# 2_cpu_control.net
KiCad netlist of a schematic drawn in EAGLE
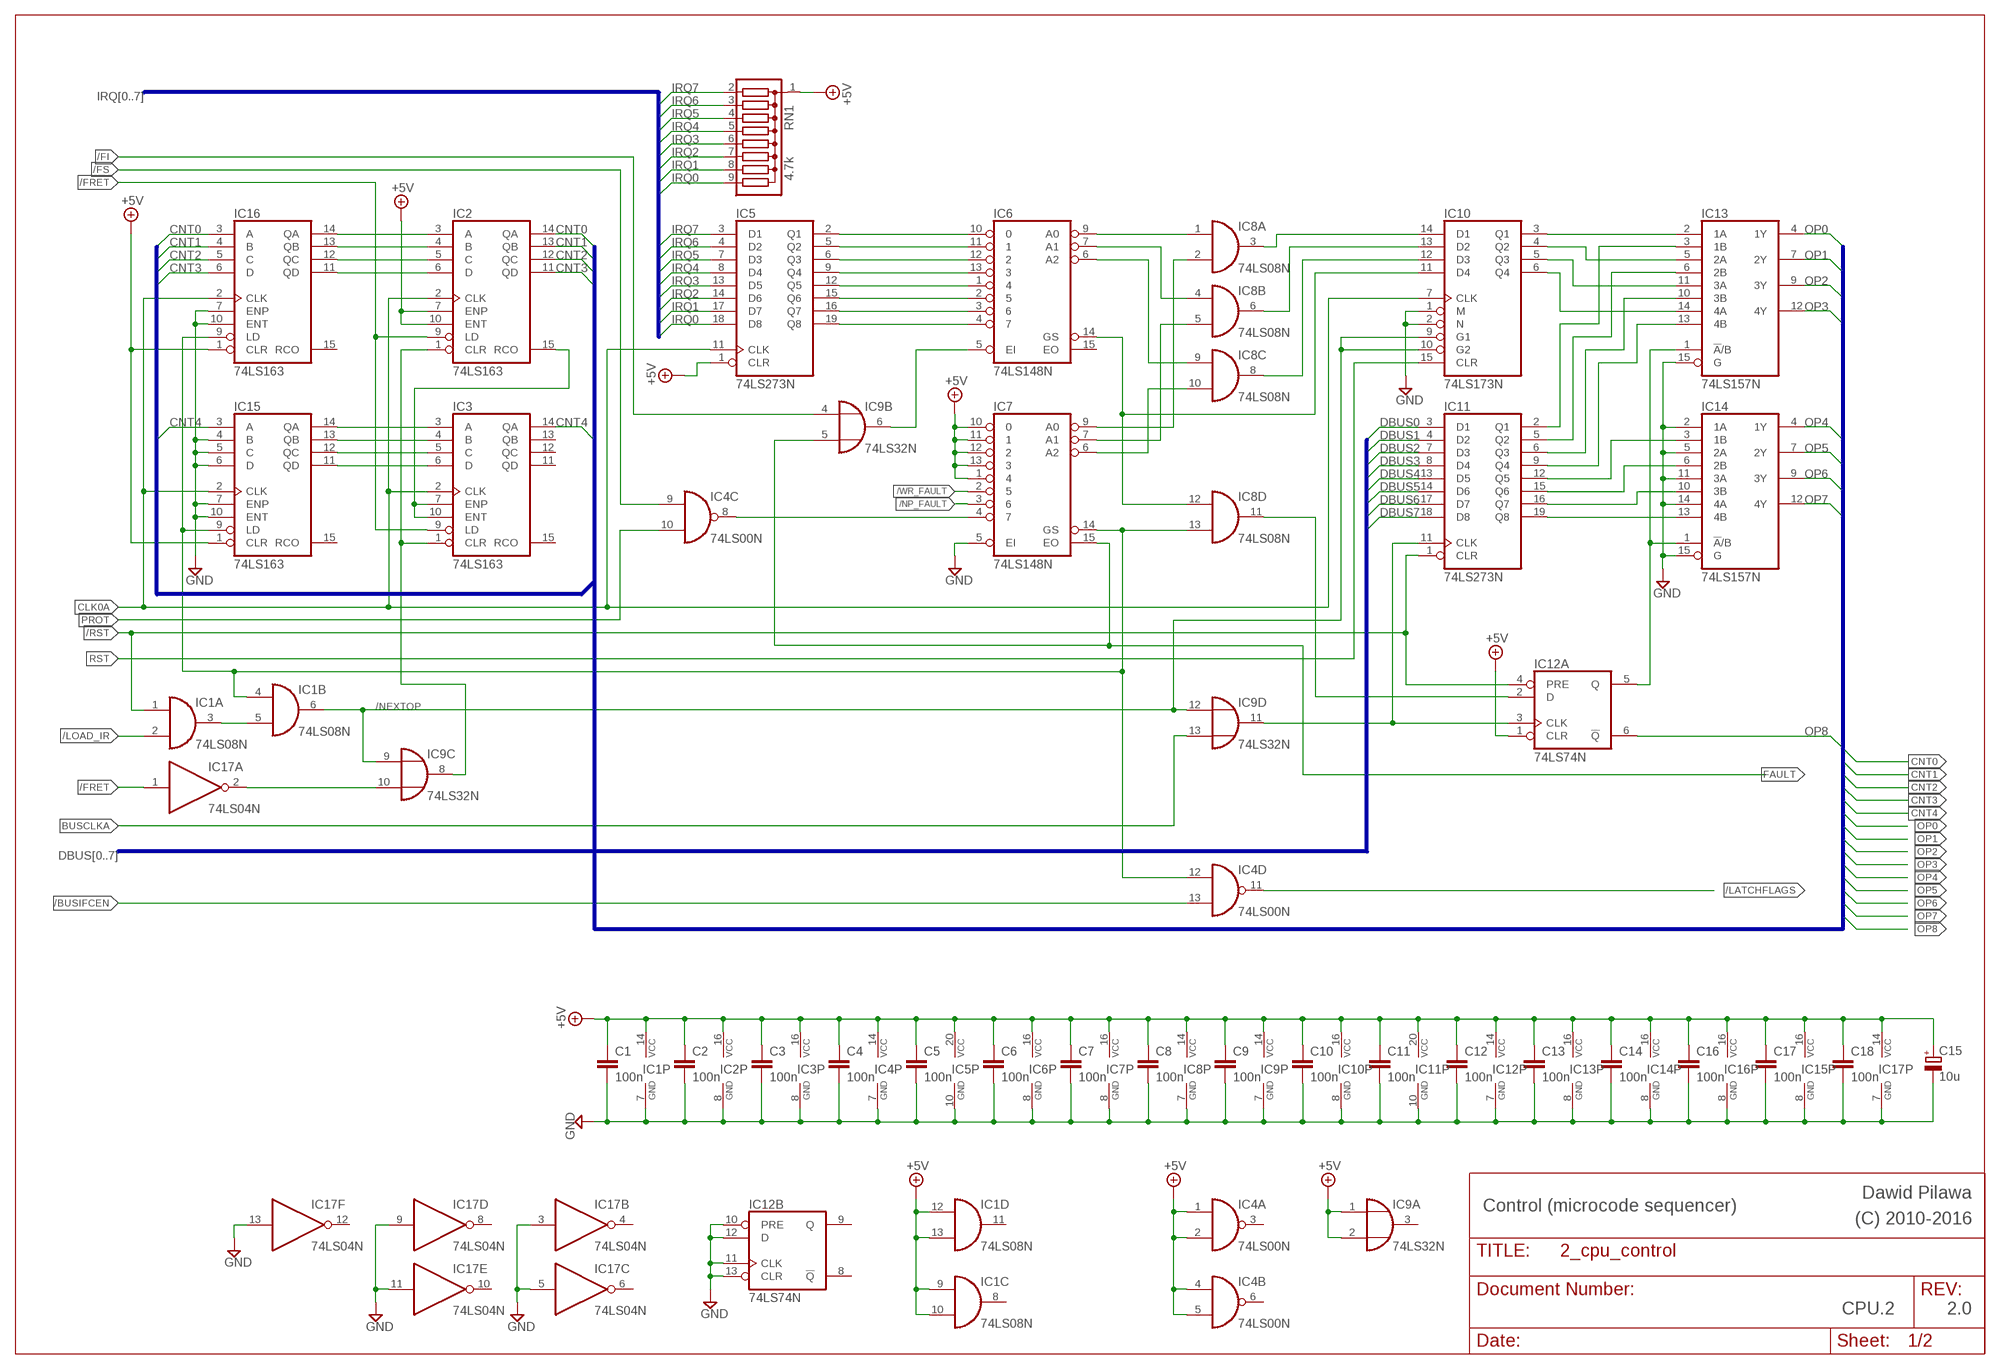
[diagram p0: schematic, sheet 1]
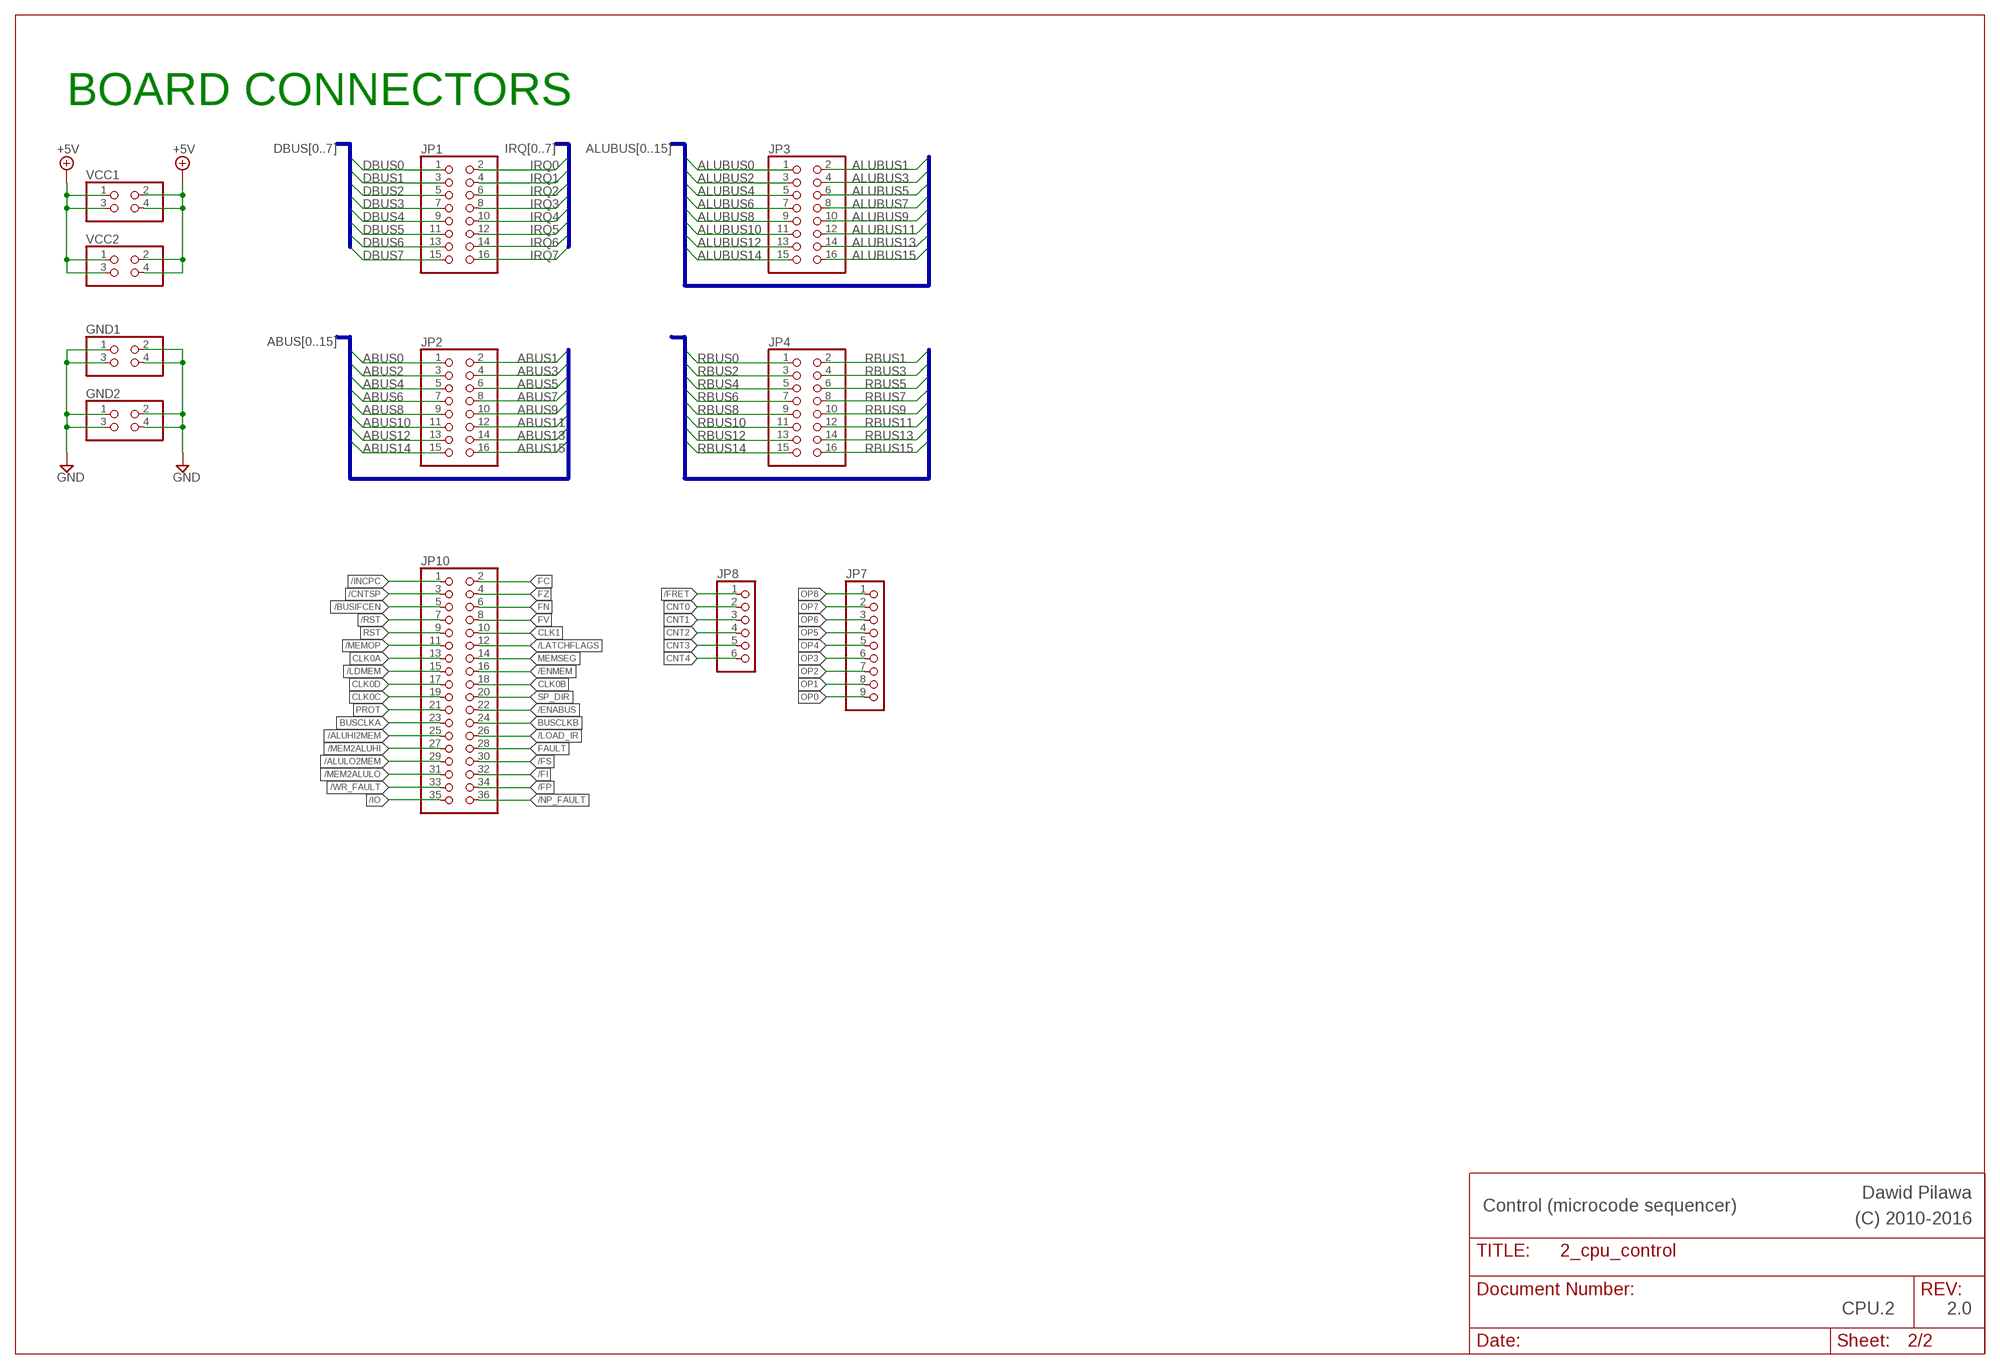
[diagram p1: schematic, sheet 2]

(export (version "E")
  (design (tool "Eeschema 10.0.6"))
  (components
    (comp (ref "C1")
      (value "100n")
      (footprint "eagle-import:C050-024X044")
      (libsource (lib "eagle-import") (part "C-EU050-024X044"))
    )
    (comp (ref "C2")
      (value "100n")
      (footprint "eagle-import:C050-024X044")
      (libsource (lib "eagle-import") (part "C-EU050-024X044"))
    )
    (comp (ref "C3")
      (value "100n")
      (footprint "eagle-import:C050-024X044")
      (libsource (lib "eagle-import") (part "C-EU050-024X044"))
    )
    (comp (ref "C4")
      (value "100n")
      (footprint "eagle-import:C050-024X044")
      (libsource (lib "eagle-import") (part "C-EU050-024X044"))
    )
    (comp (ref "C5")
      (value "100n")
      (footprint "eagle-import:C050-024X044")
      (libsource (lib "eagle-import") (part "C-EU050-024X044"))
    )
    (comp (ref "C6")
      (value "100n")
      (footprint "eagle-import:C050-024X044")
      (libsource (lib "eagle-import") (part "C-EU050-024X044"))
    )
    (comp (ref "C7")
      (value "100n")
      (footprint "eagle-import:C050-024X044")
      (libsource (lib "eagle-import") (part "C-EU050-024X044"))
    )
    (comp (ref "C8")
      (value "100n")
      (footprint "eagle-import:C050-024X044")
      (libsource (lib "eagle-import") (part "C-EU050-024X044"))
    )
    (comp (ref "C9")
      (value "100n")
      (footprint "eagle-import:C050-024X044")
      (libsource (lib "eagle-import") (part "C-EU050-024X044"))
    )
    (comp (ref "C10")
      (value "100n")
      (footprint "eagle-import:C050-024X044")
      (libsource (lib "eagle-import") (part "C-EU050-024X044"))
    )
    (comp (ref "C11")
      (value "100n")
      (footprint "eagle-import:C050-024X044")
      (libsource (lib "eagle-import") (part "C-EU050-024X044"))
    )
    (comp (ref "C12")
      (value "100n")
      (footprint "eagle-import:C050-024X044")
      (libsource (lib "eagle-import") (part "C-EU050-024X044"))
    )
    (comp (ref "C13")
      (value "100n")
      (footprint "eagle-import:C050-024X044")
      (libsource (lib "eagle-import") (part "C-EU050-024X044"))
    )
    (comp (ref "C14")
      (value "100n")
      (footprint "eagle-import:C050-024X044")
      (libsource (lib "eagle-import") (part "C-EU050-024X044"))
    )
    (comp (ref "C15")
      (value "10u")
      (footprint "eagle-import:E5-6")
      (libsource (lib "eagle-import") (part "CPOL-EUE5-6"))
    )
    (comp (ref "C16")
      (value "100n")
      (footprint "eagle-import:C050-024X044")
      (libsource (lib "eagle-import") (part "C-EU050-024X044"))
    )
    (comp (ref "C17")
      (value "100n")
      (footprint "eagle-import:C050-024X044")
      (libsource (lib "eagle-import") (part "C-EU050-024X044"))
    )
    (comp (ref "C18")
      (value "100n")
      (footprint "eagle-import:C050-024X044")
      (libsource (lib "eagle-import") (part "C-EU050-024X044"))
    )
    (comp (ref "IC1")
      (value "74LS08N")
      (footprint "eagle-import:DIL14")
      (libsource (lib "eagle-import") (part "7408NLS"))
    )
    (comp (ref "IC2")
      (value "74LS163")
      (footprint "eagle-import:DIL16")
      (libsource (lib "eagle-import") (part "74160N"))
    )
    (comp (ref "IC3")
      (value "74LS163")
      (footprint "eagle-import:DIL16")
      (libsource (lib "eagle-import") (part "74160N"))
    )
    (comp (ref "IC4")
      (value "74LS00N")
      (footprint "eagle-import:DIL14")
      (libsource (lib "eagle-import") (part "7400NLS"))
    )
    (comp (ref "IC5")
      (value "74LS273N")
      (footprint "eagle-import:DIL20")
      (libsource (lib "eagle-import") (part "74273N"))
    )
    (comp (ref "IC6")
      (value "74LS148N")
      (footprint "eagle-import:DIL16")
      (libsource (lib "eagle-import") (part "74148NLS"))
    )
    (comp (ref "IC7")
      (value "74LS148N")
      (footprint "eagle-import:DIL16")
      (libsource (lib "eagle-import") (part "74148NLS"))
    )
    (comp (ref "IC8")
      (value "74LS08N")
      (footprint "eagle-import:DIL14")
      (libsource (lib "eagle-import") (part "7408NLS"))
    )
    (comp (ref "IC9")
      (value "74LS32N")
      (footprint "eagle-import:DIL14")
      (libsource (lib "eagle-import") (part "7432NLS"))
    )
    (comp (ref "IC10")
      (value "74LS173N")
      (footprint "eagle-import:DIL16")
      (libsource (lib "eagle-import") (part "74173NLS"))
    )
    (comp (ref "IC11")
      (value "74LS273N")
      (footprint "eagle-import:DIL20")
      (libsource (lib "eagle-import") (part "74273N"))
    )
    (comp (ref "IC12")
      (value "74LS74N")
      (footprint "eagle-import:DIL14")
      (libsource (lib "eagle-import") (part "7474NLS"))
    )
    (comp (ref "IC13")
      (value "74LS157N")
      (footprint "eagle-import:DIL16")
      (libsource (lib "eagle-import") (part "74157NLS"))
    )
    (comp (ref "IC14")
      (value "74LS157N")
      (footprint "eagle-import:DIL16")
      (libsource (lib "eagle-import") (part "74157NLS"))
    )
    (comp (ref "IC15")
      (value "74LS163")
      (footprint "eagle-import:DIL16")
      (libsource (lib "eagle-import") (part "74160N"))
    )
    (comp (ref "IC16")
      (value "74LS163")
      (footprint "eagle-import:DIL16")
      (libsource (lib "eagle-import") (part "74160N"))
    )
    (comp (ref "IC17")
      (value "74LS04N")
      (footprint "eagle-import:DIL14")
      (libsource (lib "eagle-import") (part "7404NLS"))
    )
    (comp (ref "RN1")
      (value "4.7k")
      (footprint "eagle-import:SIL9")
      (libsource (lib "eagle-import") (part "G08R"))
    )
    (comp (ref "GND1")
      (value "PINHD-2X2")
      (footprint "eagle-import:2X02")
      (libsource (lib "eagle-import") (part "PINHD-2X2"))
    )
    (comp (ref "GND2")
      (value "PINHD-2X2")
      (footprint "eagle-import:2X02")
      (libsource (lib "eagle-import") (part "PINHD-2X2"))
    )
    (comp (ref "JP1")
      (value "PINHD-2X8")
      (footprint "eagle-import:2X08")
      (libsource (lib "eagle-import") (part "PINHD-2X8"))
    )
    (comp (ref "JP2")
      (value "PINHD-2X8")
      (footprint "eagle-import:2X08")
      (libsource (lib "eagle-import") (part "PINHD-2X8"))
    )
    (comp (ref "JP3")
      (value "PINHD-2X8")
      (footprint "eagle-import:2X08")
      (libsource (lib "eagle-import") (part "PINHD-2X8"))
    )
    (comp (ref "JP4")
      (value "PINHD-2X8")
      (footprint "eagle-import:2X08")
      (libsource (lib "eagle-import") (part "PINHD-2X8"))
    )
    (comp (ref "JP7")
      (value "PINHD-1X9")
      (footprint "eagle-import:1X09")
      (libsource (lib "eagle-import") (part "PINHD-1X9"))
    )
    (comp (ref "JP8")
      (value "PINHD-1X6")
      (footprint "eagle-import:1X06")
      (libsource (lib "eagle-import") (part "PINHD-1X6"))
    )
    (comp (ref "JP10")
      (value "PINHD-2X18")
      (footprint "eagle-import:2X18")
      (libsource (lib "eagle-import") (part "PINHD-2X18"))
    )
    (comp (ref "VCC1")
      (value "PINHD-2X2")
      (footprint "eagle-import:2X02")
      (libsource (lib "eagle-import") (part "PINHD-2X2"))
    )
    (comp (ref "VCC2")
      (value "PINHD-2X2")
      (footprint "eagle-import:2X02")
      (libsource (lib "eagle-import") (part "PINHD-2X2"))
    )
  )
  (nets
    (net (code "1") (name "+5V") (class "Default")
      (node (ref "C1") (pin "1") (pinfunction "1_1") (pintype "passive"))
      (node (ref "C10") (pin "1") (pinfunction "1_1") (pintype "passive"))
      (node (ref "C11") (pin "1") (pinfunction "1_1") (pintype "passive"))
      (node (ref "C12") (pin "1") (pinfunction "1_1") (pintype "passive"))
      (node (ref "C13") (pin "1") (pinfunction "1_1") (pintype "passive"))
      (node (ref "C14") (pin "1") (pinfunction "1_1") (pintype "passive"))
      (node (ref "C15") (pin "+") (pinfunction "+_+") (pintype "passive"))
      (node (ref "C16") (pin "1") (pinfunction "1_1") (pintype "passive"))
      (node (ref "C17") (pin "1") (pinfunction "1_1") (pintype "passive"))
      (node (ref "C18") (pin "1") (pinfunction "1_1") (pintype "passive"))
      (node (ref "C2") (pin "1") (pinfunction "1_1") (pintype "passive"))
      (node (ref "C3") (pin "1") (pinfunction "1_1") (pintype "passive"))
      (node (ref "C4") (pin "1") (pinfunction "1_1") (pintype "passive"))
      (node (ref "C5") (pin "1") (pinfunction "1_1") (pintype "passive"))
      (node (ref "C6") (pin "1") (pinfunction "1_1") (pintype "passive"))
      (node (ref "C7") (pin "1") (pinfunction "1_1") (pintype "passive"))
      (node (ref "C8") (pin "1") (pinfunction "1_1") (pintype "passive"))
      (node (ref "C9") (pin "1") (pinfunction "1_1") (pintype "passive"))
      (node (ref "IC1") (pin "10") (pinfunction "I1_10") (pintype "input"))
      (node (ref "IC1") (pin "12") (pinfunction "I0_12") (pintype "input"))
      (node (ref "IC1") (pin "13") (pinfunction "I1_13") (pintype "input"))
      (node (ref "IC1") (pin "14") (pinfunction "VCC_14") (pintype "power_in"))
      (node (ref "IC1") (pin "9") (pinfunction "I0_9") (pintype "input"))
      (node (ref "IC10") (pin "16") (pinfunction "VCC_16") (pintype "power_in"))
      (node (ref "IC11") (pin "20") (pinfunction "VCC_20") (pintype "power_in"))
      (node (ref "IC12") (pin "1") (pinfunction "CLR_1") (pintype "input"))
      (node (ref "IC12") (pin "14") (pinfunction "VCC_14") (pintype "power_in"))
      (node (ref "IC13") (pin "16") (pinfunction "VCC_16") (pintype "power_in"))
      (node (ref "IC14") (pin "16") (pinfunction "VCC_16") (pintype "power_in"))
      (node (ref "IC15") (pin "1") (pinfunction "CLR_1") (pintype "input"))
      (node (ref "IC15") (pin "16") (pinfunction "VCC_16") (pintype "power_in"))
      (node (ref "IC16") (pin "1") (pinfunction "CLR_1") (pintype "input"))
      (node (ref "IC16") (pin "16") (pinfunction "VCC_16") (pintype "power_in"))
      (node (ref "IC17") (pin "14") (pinfunction "VCC_14") (pintype "power_in"))
      (node (ref "IC2") (pin "10") (pinfunction "ENT_10") (pintype "input"))
      (node (ref "IC2") (pin "16") (pinfunction "VCC_16") (pintype "power_in"))
      (node (ref "IC2") (pin "7") (pinfunction "ENP_7") (pintype "input"))
      (node (ref "IC3") (pin "16") (pinfunction "VCC_16") (pintype "power_in"))
      (node (ref "IC4") (pin "1") (pinfunction "I0_1") (pintype "input"))
      (node (ref "IC4") (pin "14") (pinfunction "VCC_14") (pintype "power_in"))
      (node (ref "IC4") (pin "2") (pinfunction "I1_2") (pintype "input"))
      (node (ref "IC4") (pin "4") (pinfunction "I0_4") (pintype "input"))
      (node (ref "IC4") (pin "5") (pinfunction "I1_5") (pintype "input"))
      (node (ref "IC5") (pin "1") (pinfunction "CLR_1") (pintype "input"))
      (node (ref "IC5") (pin "20") (pinfunction "VCC_20") (pintype "power_in"))
      (node (ref "IC6") (pin "16") (pinfunction "VCC_16") (pintype "power_in"))
      (node (ref "IC7") (pin "1") (pinfunction "4_1") (pintype "input"))
      (node (ref "IC7") (pin "10") (pinfunction "0_10") (pintype "input"))
      (node (ref "IC7") (pin "11") (pinfunction "1_11") (pintype "input"))
      (node (ref "IC7") (pin "12") (pinfunction "2_12") (pintype "input"))
      (node (ref "IC7") (pin "13") (pinfunction "3_13") (pintype "input"))
      (node (ref "IC7") (pin "16") (pinfunction "VCC_16") (pintype "power_in"))
      (node (ref "IC8") (pin "14") (pinfunction "VCC_14") (pintype "power_in"))
      (node (ref "IC9") (pin "1") (pinfunction "I0_1") (pintype "input"))
      (node (ref "IC9") (pin "14") (pinfunction "VCC_14") (pintype "power_in"))
      (node (ref "IC9") (pin "2") (pinfunction "I1_2") (pintype "input"))
      (node (ref "RN1") (pin "1") (pinfunction "1_1") (pintype "passive"))
      (node (ref "VCC1") (pin "1") (pinfunction "1_1") (pintype "passive"))
      (node (ref "VCC1") (pin "2") (pinfunction "2_2") (pintype "passive"))
      (node (ref "VCC1") (pin "3") (pinfunction "3_3") (pintype "passive"))
      (node (ref "VCC1") (pin "4") (pinfunction "4_4") (pintype "passive"))
      (node (ref "VCC2") (pin "1") (pinfunction "1_1") (pintype "passive"))
      (node (ref "VCC2") (pin "2") (pinfunction "2_2") (pintype "passive"))
      (node (ref "VCC2") (pin "3") (pinfunction "3_3") (pintype "passive"))
      (node (ref "VCC2") (pin "4") (pinfunction "4_4") (pintype "passive"))
    )
    (net (code "8") (name "ABUS0") (class "Default")
      (node (ref "JP2") (pin "1") (pinfunction "1_1") (pintype "passive"))
    )
    (net (code "9") (name "ABUS1") (class "Default")
      (node (ref "JP2") (pin "2") (pinfunction "2_2") (pintype "passive"))
    )
    (net (code "10") (name "ABUS2") (class "Default")
      (node (ref "JP2") (pin "3") (pinfunction "3_3") (pintype "passive"))
    )
    (net (code "11") (name "ABUS3") (class "Default")
      (node (ref "JP2") (pin "4") (pinfunction "4_4") (pintype "passive"))
    )
    (net (code "12") (name "ABUS4") (class "Default")
      (node (ref "JP2") (pin "5") (pinfunction "5_5") (pintype "passive"))
    )
    (net (code "13") (name "ABUS5") (class "Default")
      (node (ref "JP2") (pin "6") (pinfunction "6_6") (pintype "passive"))
    )
    (net (code "14") (name "ABUS6") (class "Default")
      (node (ref "JP2") (pin "7") (pinfunction "7_7") (pintype "passive"))
    )
    (net (code "15") (name "ABUS7") (class "Default")
      (node (ref "JP2") (pin "8") (pinfunction "8_8") (pintype "passive"))
    )
    (net (code "16") (name "ABUS8") (class "Default")
      (node (ref "JP2") (pin "9") (pinfunction "9_9") (pintype "passive"))
    )
    (net (code "17") (name "ABUS9") (class "Default")
      (node (ref "JP2") (pin "10") (pinfunction "10_10") (pintype "passive"))
    )
    (net (code "18") (name "ABUS10") (class "Default")
      (node (ref "JP2") (pin "11") (pinfunction "11_11") (pintype "passive"))
    )
    (net (code "19") (name "ABUS11") (class "Default")
      (node (ref "JP2") (pin "12") (pinfunction "12_12") (pintype "passive"))
    )
    (net (code "20") (name "ABUS12") (class "Default")
      (node (ref "JP2") (pin "13") (pinfunction "13_13") (pintype "passive"))
    )
    (net (code "21") (name "ABUS13") (class "Default")
      (node (ref "JP2") (pin "14") (pinfunction "14_14") (pintype "passive"))
    )
    (net (code "22") (name "ABUS14") (class "Default")
      (node (ref "JP2") (pin "15") (pinfunction "15_15") (pintype "passive"))
    )
    (net (code "23") (name "ABUS15") (class "Default")
      (node (ref "JP2") (pin "16") (pinfunction "16_16") (pintype "passive"))
    )
    (net (code "24") (name "ALUBUS0") (class "Default")
      (node (ref "JP3") (pin "1") (pinfunction "1_1") (pintype "passive"))
    )
    (net (code "25") (name "ALUBUS1") (class "Default")
      (node (ref "JP3") (pin "2") (pinfunction "2_2") (pintype "passive"))
    )
    (net (code "26") (name "ALUBUS2") (class "Default")
      (node (ref "JP3") (pin "3") (pinfunction "3_3") (pintype "passive"))
    )
    (net (code "27") (name "ALUBUS3") (class "Default")
      (node (ref "JP3") (pin "4") (pinfunction "4_4") (pintype "passive"))
    )
    (net (code "28") (name "ALUBUS4") (class "Default")
      (node (ref "JP3") (pin "5") (pinfunction "5_5") (pintype "passive"))
    )
    (net (code "29") (name "ALUBUS5") (class "Default")
      (node (ref "JP3") (pin "6") (pinfunction "6_6") (pintype "passive"))
    )
    (net (code "30") (name "ALUBUS6") (class "Default")
      (node (ref "JP3") (pin "7") (pinfunction "7_7") (pintype "passive"))
    )
    (net (code "31") (name "ALUBUS7") (class "Default")
      (node (ref "JP3") (pin "8") (pinfunction "8_8") (pintype "passive"))
    )
    (net (code "32") (name "ALUBUS8") (class "Default")
      (node (ref "JP3") (pin "9") (pinfunction "9_9") (pintype "passive"))
    )
    (net (code "33") (name "ALUBUS9") (class "Default")
      (node (ref "JP3") (pin "10") (pinfunction "10_10") (pintype "passive"))
    )
    (net (code "34") (name "ALUBUS10") (class "Default")
      (node (ref "JP3") (pin "11") (pinfunction "11_11") (pintype "passive"))
    )
    (net (code "35") (name "ALUBUS11") (class "Default")
      (node (ref "JP3") (pin "12") (pinfunction "12_12") (pintype "passive"))
    )
    (net (code "36") (name "ALUBUS12") (class "Default")
      (node (ref "JP3") (pin "13") (pinfunction "13_13") (pintype "passive"))
    )
    (net (code "37") (name "ALUBUS13") (class "Default")
      (node (ref "JP3") (pin "14") (pinfunction "14_14") (pintype "passive"))
    )
    (net (code "38") (name "ALUBUS14") (class "Default")
      (node (ref "JP3") (pin "15") (pinfunction "15_15") (pintype "passive"))
    )
    (net (code "39") (name "ALUBUS15") (class "Default")
      (node (ref "JP3") (pin "16") (pinfunction "16_16") (pintype "passive"))
    )
    (net (code "40") (name "BUSCLKA") (class "Default")
      (node (ref "IC9") (pin "13") (pinfunction "I1_13") (pintype "input"))
      (node (ref "JP10") (pin "23") (pinfunction "23_23") (pintype "passive"))
    )
    (net (code "41") (name "BUSCLKB") (class "Default")
      (node (ref "JP10") (pin "24") (pinfunction "24_24") (pintype "passive"))
    )
    (net (code "42") (name "CLK0A") (class "Default")
      (node (ref "IC10") (pin "7") (pinfunction "CLK_7") (pintype "input"))
      (node (ref "IC15") (pin "2") (pinfunction "CLK_2") (pintype "input"))
      (node (ref "IC16") (pin "2") (pinfunction "CLK_2") (pintype "input"))
      (node (ref "IC2") (pin "2") (pinfunction "CLK_2") (pintype "input"))
      (node (ref "IC3") (pin "2") (pinfunction "CLK_2") (pintype "input"))
      (node (ref "IC5") (pin "11") (pinfunction "CLK_11") (pintype "input"))
      (node (ref "JP10") (pin "13") (pinfunction "13_13") (pintype "passive"))
    )
    (net (code "43") (name "CLK0B") (class "Default")
      (node (ref "JP10") (pin "18") (pinfunction "18_18") (pintype "passive"))
    )
    (net (code "44") (name "CLK0C") (class "Default")
      (node (ref "JP10") (pin "19") (pinfunction "19_19") (pintype "passive"))
    )
    (net (code "45") (name "CLK0D") (class "Default")
      (node (ref "JP10") (pin "17") (pinfunction "17_17") (pintype "passive"))
    )
    (net (code "46") (name "CLK1") (class "Default")
      (node (ref "JP10") (pin "10") (pinfunction "10_10") (pintype "passive"))
    )
    (net (code "47") (name "CNT0") (class "Default")
      (node (ref "IC16") (pin "3") (pinfunction "A_3") (pintype "input"))
      (node (ref "IC2") (pin "14") (pinfunction "QA_14") (pintype "output"))
      (node (ref "JP8") (pin "2") (pinfunction "2_2") (pintype "passive"))
    )
    (net (code "48") (name "CNT1") (class "Default")
      (node (ref "IC16") (pin "4") (pinfunction "B_4") (pintype "input"))
      (node (ref "IC2") (pin "13") (pinfunction "QB_13") (pintype "output"))
      (node (ref "JP8") (pin "3") (pinfunction "3_3") (pintype "passive"))
    )
    (net (code "49") (name "CNT2") (class "Default")
      (node (ref "IC16") (pin "5") (pinfunction "C_5") (pintype "input"))
      (node (ref "IC2") (pin "12") (pinfunction "QC_12") (pintype "output"))
      (node (ref "JP8") (pin "4") (pinfunction "4_4") (pintype "passive"))
    )
    (net (code "50") (name "CNT3") (class "Default")
      (node (ref "IC16") (pin "6") (pinfunction "D_6") (pintype "input"))
      (node (ref "IC2") (pin "11") (pinfunction "QD_11") (pintype "output"))
      (node (ref "JP8") (pin "5") (pinfunction "5_5") (pintype "passive"))
    )
    (net (code "51") (name "CNT4") (class "Default")
      (node (ref "IC15") (pin "3") (pinfunction "A_3") (pintype "input"))
      (node (ref "IC3") (pin "14") (pinfunction "QA_14") (pintype "output"))
      (node (ref "JP8") (pin "6") (pinfunction "6_6") (pintype "passive"))
    )
    (net (code "52") (name "DBUS0") (class "Default")
      (node (ref "IC11") (pin "3") (pinfunction "D1_3") (pintype "input"))
      (node (ref "JP1") (pin "1") (pinfunction "1_1") (pintype "passive"))
    )
    (net (code "53") (name "DBUS1") (class "Default")
      (node (ref "IC11") (pin "4") (pinfunction "D2_4") (pintype "input"))
      (node (ref "JP1") (pin "3") (pinfunction "3_3") (pintype "passive"))
    )
    (net (code "54") (name "DBUS2") (class "Default")
      (node (ref "IC11") (pin "7") (pinfunction "D3_7") (pintype "input"))
      (node (ref "JP1") (pin "5") (pinfunction "5_5") (pintype "passive"))
    )
    (net (code "55") (name "DBUS3") (class "Default")
      (node (ref "IC11") (pin "8") (pinfunction "D4_8") (pintype "input"))
      (node (ref "JP1") (pin "7") (pinfunction "7_7") (pintype "passive"))
    )
    (net (code "56") (name "DBUS4") (class "Default")
      (node (ref "IC11") (pin "13") (pinfunction "D5_13") (pintype "input"))
      (node (ref "JP1") (pin "9") (pinfunction "9_9") (pintype "passive"))
    )
    (net (code "57") (name "DBUS5") (class "Default")
      (node (ref "IC11") (pin "14") (pinfunction "D6_14") (pintype "input"))
      (node (ref "JP1") (pin "11") (pinfunction "11_11") (pintype "passive"))
    )
    (net (code "58") (name "DBUS6") (class "Default")
      (node (ref "IC11") (pin "17") (pinfunction "D7_17") (pintype "input"))
      (node (ref "JP1") (pin "13") (pinfunction "13_13") (pintype "passive"))
    )
    (net (code "59") (name "DBUS7") (class "Default")
      (node (ref "IC11") (pin "18") (pinfunction "D8_18") (pintype "input"))
      (node (ref "JP1") (pin "15") (pinfunction "15_15") (pintype "passive"))
    )
    (net (code "60") (name "FAULT") (class "Default")
      (node (ref "IC7") (pin "15") (pinfunction "EO_15") (pintype "output"))
      (node (ref "IC9") (pin "5") (pinfunction "I1_5") (pintype "input"))
      (node (ref "JP10") (pin "28") (pinfunction "28_28") (pintype "passive"))
    )
    (net (code "61") (name "FC") (class "Default")
      (node (ref "JP10") (pin "2") (pinfunction "2_2") (pintype "passive"))
    )
    (net (code "62") (name "FN") (class "Default")
      (node (ref "JP10") (pin "6") (pinfunction "6_6") (pintype "passive"))
    )
    (net (code "63") (name "FV") (class "Default")
      (node (ref "JP10") (pin "8") (pinfunction "8_8") (pintype "passive"))
    )
    (net (code "64") (name "FZ") (class "Default")
      (node (ref "JP10") (pin "4") (pinfunction "4_4") (pintype "passive"))
    )
    (net (code "65") (name "GND") (class "Default")
      (node (ref "C1") (pin "2") (pinfunction "2_2") (pintype "passive"))
      (node (ref "C10") (pin "2") (pinfunction "2_2") (pintype "passive"))
      (node (ref "C11") (pin "2") (pinfunction "2_2") (pintype "passive"))
      (node (ref "C12") (pin "2") (pinfunction "2_2") (pintype "passive"))
      (node (ref "C13") (pin "2") (pinfunction "2_2") (pintype "passive"))
      (node (ref "C14") (pin "2") (pinfunction "2_2") (pintype "passive"))
      (node (ref "C15") (pin "-") (pinfunction "-_-") (pintype "passive"))
      (node (ref "C16") (pin "2") (pinfunction "2_2") (pintype "passive"))
      (node (ref "C17") (pin "2") (pinfunction "2_2") (pintype "passive"))
      (node (ref "C18") (pin "2") (pinfunction "2_2") (pintype "passive"))
      (node (ref "C2") (pin "2") (pinfunction "2_2") (pintype "passive"))
      (node (ref "C3") (pin "2") (pinfunction "2_2") (pintype "passive"))
      (node (ref "C4") (pin "2") (pinfunction "2_2") (pintype "passive"))
      (node (ref "C5") (pin "2") (pinfunction "2_2") (pintype "passive"))
      (node (ref "C6") (pin "2") (pinfunction "2_2") (pintype "passive"))
      (node (ref "C7") (pin "2") (pinfunction "2_2") (pintype "passive"))
      (node (ref "C8") (pin "2") (pinfunction "2_2") (pintype "passive"))
      (node (ref "C9") (pin "2") (pinfunction "2_2") (pintype "passive"))
      (node (ref "GND1") (pin "1") (pinfunction "1_1") (pintype "passive"))
      (node (ref "GND1") (pin "2") (pinfunction "2_2") (pintype "passive"))
      (node (ref "GND1") (pin "3") (pinfunction "3_3") (pintype "passive"))
      (node (ref "GND1") (pin "4") (pinfunction "4_4") (pintype "passive"))
      (node (ref "GND2") (pin "1") (pinfunction "1_1") (pintype "passive"))
      (node (ref "GND2") (pin "2") (pinfunction "2_2") (pintype "passive"))
      (node (ref "GND2") (pin "3") (pinfunction "3_3") (pintype "passive"))
      (node (ref "GND2") (pin "4") (pinfunction "4_4") (pintype "passive"))
      (node (ref "IC1") (pin "7") (pinfunction "GND_7") (pintype "power_in"))
      (node (ref "IC10") (pin "1") (pinfunction "M_1") (pintype "input"))
      (node (ref "IC10") (pin "2") (pinfunction "N_2") (pintype "input"))
      (node (ref "IC10") (pin "8") (pinfunction "GND_8") (pintype "power_in"))
      (node (ref "IC11") (pin "10") (pinfunction "GND_10") (pintype "power_in"))
      (node (ref "IC12") (pin "10") (pinfunction "PRE_10") (pintype "input"))
      (node (ref "IC12") (pin "11") (pinfunction "CLK_11") (pintype "input"))
      (node (ref "IC12") (pin "12") (pinfunction "D_12") (pintype "input"))
      (node (ref "IC12") (pin "13") (pinfunction "CLR_13") (pintype "input"))
      (node (ref "IC12") (pin "7") (pinfunction "GND_7") (pintype "power_in"))
      (node (ref "IC13") (pin "15") (pinfunction "G_15") (pintype "input"))
      (node (ref "IC13") (pin "8") (pinfunction "GND_8") (pintype "power_in"))
      (node (ref "IC14") (pin "11") (pinfunction "3A_11") (pintype "input"))
      (node (ref "IC14") (pin "14") (pinfunction "4A_14") (pintype "input"))
      (node (ref "IC14") (pin "15") (pinfunction "G_15") (pintype "input"))
      (node (ref "IC14") (pin "2") (pinfunction "1A_2") (pintype "input"))
      (node (ref "IC14") (pin "5") (pinfunction "2A_5") (pintype "input"))
      (node (ref "IC14") (pin "8") (pinfunction "GND_8") (pintype "power_in"))
      (node (ref "IC15") (pin "10") (pinfunction "ENT_10") (pintype "input"))
      (node (ref "IC15") (pin "4") (pinfunction "B_4") (pintype "input"))
      (node (ref "IC15") (pin "5") (pinfunction "C_5") (pintype "input"))
      (node (ref "IC15") (pin "6") (pinfunction "D_6") (pintype "input"))
      (node (ref "IC15") (pin "7") (pinfunction "ENP_7") (pintype "input"))
      (node (ref "IC15") (pin "8") (pinfunction "GND_8") (pintype "power_in"))
      (node (ref "IC16") (pin "10") (pinfunction "ENT_10") (pintype "input"))
      (node (ref "IC16") (pin "7") (pinfunction "ENP_7") (pintype "input"))
      (node (ref "IC16") (pin "8") (pinfunction "GND_8") (pintype "power_in"))
      (node (ref "IC17") (pin "11") (pinfunction "I_11") (pintype "input"))
      (node (ref "IC17") (pin "13") (pinfunction "I_13") (pintype "input"))
      (node (ref "IC17") (pin "3") (pinfunction "I_3") (pintype "input"))
      (node (ref "IC17") (pin "5") (pinfunction "I_5") (pintype "input"))
      (node (ref "IC17") (pin "7") (pinfunction "GND_7") (pintype "power_in"))
      (node (ref "IC17") (pin "9") (pinfunction "I_9") (pintype "input"))
      (node (ref "IC2") (pin "8") (pinfunction "GND_8") (pintype "power_in"))
      (node (ref "IC3") (pin "8") (pinfunction "GND_8") (pintype "power_in"))
      (node (ref "IC4") (pin "7") (pinfunction "GND_7") (pintype "power_in"))
      (node (ref "IC5") (pin "10") (pinfunction "GND_10") (pintype "power_in"))
      (node (ref "IC6") (pin "8") (pinfunction "GND_8") (pintype "power_in"))
      (node (ref "IC7") (pin "5") (pinfunction "EI_5") (pintype "input"))
      (node (ref "IC7") (pin "8") (pinfunction "GND_8") (pintype "power_in"))
      (node (ref "IC8") (pin "7") (pinfunction "GND_7") (pintype "power_in"))
      (node (ref "IC9") (pin "7") (pinfunction "GND_7") (pintype "power_in"))
    )
    (net (code "66") (name "IRQ0") (class "Default")
      (node (ref "IC5") (pin "18") (pinfunction "D8_18") (pintype "input"))
      (node (ref "JP1") (pin "2") (pinfunction "2_2") (pintype "passive"))
      (node (ref "RN1") (pin "9") (pinfunction "9_9") (pintype "passive"))
    )
    (net (code "67") (name "IRQ1") (class "Default")
      (node (ref "IC5") (pin "17") (pinfunction "D7_17") (pintype "input"))
      (node (ref "JP1") (pin "4") (pinfunction "4_4") (pintype "passive"))
      (node (ref "RN1") (pin "8") (pinfunction "8_8") (pintype "passive"))
    )
    (net (code "68") (name "IRQ2") (class "Default")
      (node (ref "IC5") (pin "14") (pinfunction "D6_14") (pintype "input"))
      (node (ref "JP1") (pin "6") (pinfunction "6_6") (pintype "passive"))
      (node (ref "RN1") (pin "7") (pinfunction "7_7") (pintype "passive"))
    )
    (net (code "69") (name "IRQ3") (class "Default")
      (node (ref "IC5") (pin "13") (pinfunction "D5_13") (pintype "input"))
      (node (ref "JP1") (pin "8") (pinfunction "8_8") (pintype "passive"))
      (node (ref "RN1") (pin "6") (pinfunction "6_6") (pintype "passive"))
    )
    (net (code "70") (name "IRQ4") (class "Default")
      (node (ref "IC5") (pin "8") (pinfunction "D4_8") (pintype "input"))
      (node (ref "JP1") (pin "10") (pinfunction "10_10") (pintype "passive"))
      (node (ref "RN1") (pin "5") (pinfunction "5_5") (pintype "passive"))
    )
    (net (code "71") (name "IRQ5") (class "Default")
      (node (ref "IC5") (pin "7") (pinfunction "D3_7") (pintype "input"))
      (node (ref "JP1") (pin "12") (pinfunction "12_12") (pintype "passive"))
      (node (ref "RN1") (pin "4") (pinfunction "4_4") (pintype "passive"))
    )
    (net (code "72") (name "IRQ6") (class "Default")
      (node (ref "IC5") (pin "4") (pinfunction "D2_4") (pintype "input"))
      (node (ref "JP1") (pin "14") (pinfunction "14_14") (pintype "passive"))
      (node (ref "RN1") (pin "3") (pinfunction "3_3") (pintype "passive"))
    )
    (net (code "73") (name "IRQ7") (class "Default")
      (node (ref "IC5") (pin "3") (pinfunction "D1_3") (pintype "input"))
      (node (ref "JP1") (pin "16") (pinfunction "16_16") (pintype "passive"))
      (node (ref "RN1") (pin "2") (pinfunction "2_2") (pintype "passive"))
    )
    (net (code "74") (name "MEMSEG") (class "Default")
      (node (ref "JP10") (pin "14") (pinfunction "14_14") (pintype "passive"))
    )
    (net (code "75") (name "Net-(IC1A-O)") (class "Default")
      (node (ref "IC1") (pin "3") (pinfunction "O_3") (pintype "output"))
      (node (ref "IC1") (pin "5") (pinfunction "I1_5") (pintype "input"))
    )
    (net (code "76") (name "Net-(IC2A-CLR)") (class "Default")
      (node (ref "IC2") (pin "1") (pinfunction "CLR_1") (pintype "input"))
      (node (ref "IC3") (pin "1") (pinfunction "CLR_1") (pintype "input"))
      (node (ref "IC9") (pin "8") (pinfunction "O_8") (pintype "output"))
    )
    (net (code "77") (name "Net-(IC2A-RCO)") (class "Default")
      (node (ref "IC2") (pin "15") (pinfunction "RCO_15") (pintype "output"))
      (node (ref "IC3") (pin "10") (pinfunction "ENT_10") (pintype "input"))
      (node (ref "IC3") (pin "7") (pinfunction "ENP_7") (pintype "input"))
    )
    (net (code "78") (name "Net-(IC4C-O)") (class "Default")
      (node (ref "IC4") (pin "8") (pinfunction "O_8") (pintype "output"))
      (node (ref "IC7") (pin "4") (pinfunction "7_4") (pintype "input"))
    )
    (net (code "79") (name "Net-(IC5A-Q1)") (class "Default")
      (node (ref "IC5") (pin "2") (pinfunction "Q1_2") (pintype "output"))
      (node (ref "IC6") (pin "10") (pinfunction "0_10") (pintype "input"))
    )
    (net (code "80") (name "Net-(IC5A-Q2)") (class "Default")
      (node (ref "IC5") (pin "5") (pinfunction "Q2_5") (pintype "output"))
      (node (ref "IC6") (pin "11") (pinfunction "1_11") (pintype "input"))
    )
    (net (code "81") (name "Net-(IC5A-Q3)") (class "Default")
      (node (ref "IC5") (pin "6") (pinfunction "Q3_6") (pintype "output"))
      (node (ref "IC6") (pin "12") (pinfunction "2_12") (pintype "input"))
    )
    (net (code "82") (name "Net-(IC5A-Q4)") (class "Default")
      (node (ref "IC5") (pin "9") (pinfunction "Q4_9") (pintype "output"))
      (node (ref "IC6") (pin "13") (pinfunction "3_13") (pintype "input"))
    )
    (net (code "83") (name "Net-(IC5A-Q5)") (class "Default")
      (node (ref "IC5") (pin "12") (pinfunction "Q5_12") (pintype "output"))
      (node (ref "IC6") (pin "1") (pinfunction "4_1") (pintype "input"))
    )
    (net (code "84") (name "Net-(IC5A-Q6)") (class "Default")
      (node (ref "IC5") (pin "15") (pinfunction "Q6_15") (pintype "output"))
      (node (ref "IC6") (pin "2") (pinfunction "5_2") (pintype "input"))
    )
    (net (code "85") (name "Net-(IC5A-Q7)") (class "Default")
      (node (ref "IC5") (pin "16") (pinfunction "Q7_16") (pintype "output"))
      (node (ref "IC6") (pin "3") (pinfunction "6_3") (pintype "input"))
    )
    (net (code "86") (name "Net-(IC5A-Q8)") (class "Default")
      (node (ref "IC5") (pin "19") (pinfunction "Q8_19") (pintype "output"))
      (node (ref "IC6") (pin "4") (pinfunction "7_4") (pintype "input"))
    )
    (net (code "87") (name "Net-(IC6A-A0)") (class "Default")
      (node (ref "IC6") (pin "9") (pinfunction "A0_9") (pintype "output"))
      (node (ref "IC8") (pin "1") (pinfunction "I0_1") (pintype "input"))
    )
    (net (code "88") (name "Net-(IC6A-A1)") (class "Default")
      (node (ref "IC6") (pin "7") (pinfunction "A1_7") (pintype "output"))
      (node (ref "IC8") (pin "4") (pinfunction "I0_4") (pintype "input"))
    )
    (net (code "89") (name "Net-(IC6A-A2)") (class "Default")
      (node (ref "IC6") (pin "6") (pinfunction "A2_6") (pintype "output"))
      (node (ref "IC8") (pin "9") (pinfunction "I0_9") (pintype "input"))
    )
    (net (code "90") (name "Net-(IC6A-EI)") (class "Default")
      (node (ref "IC6") (pin "5") (pinfunction "EI_5") (pintype "input"))
      (node (ref "IC9") (pin "6") (pinfunction "O_6") (pintype "output"))
    )
    (net (code "91") (name "Net-(IC7A-A0)") (class "Default")
      (node (ref "IC7") (pin "9") (pinfunction "A0_9") (pintype "output"))
      (node (ref "IC8") (pin "2") (pinfunction "I1_2") (pintype "input"))
    )
    (net (code "92") (name "Net-(IC7A-A1)") (class "Default")
      (node (ref "IC7") (pin "7") (pinfunction "A1_7") (pintype "output"))
      (node (ref "IC8") (pin "5") (pinfunction "I1_5") (pintype "input"))
    )
    (net (code "93") (name "Net-(IC7A-A2)") (class "Default")
      (node (ref "IC7") (pin "6") (pinfunction "A2_6") (pintype "output"))
      (node (ref "IC8") (pin "10") (pinfunction "I1_10") (pintype "input"))
    )
    (net (code "94") (name "Net-(IC10A-D1)") (class "Default")
      (node (ref "IC10") (pin "14") (pinfunction "D1_14") (pintype "input"))
      (node (ref "IC8") (pin "3") (pinfunction "O_3") (pintype "output"))
    )
    (net (code "95") (name "Net-(IC10A-D2)") (class "Default")
      (node (ref "IC10") (pin "13") (pinfunction "D2_13") (pintype "input"))
      (node (ref "IC8") (pin "6") (pinfunction "O_6") (pintype "output"))
    )
    (net (code "96") (name "Net-(IC10A-D3)") (class "Default")
      (node (ref "IC10") (pin "12") (pinfunction "D3_12") (pintype "input"))
      (node (ref "IC8") (pin "8") (pinfunction "O_8") (pintype "output"))
    )
    (net (code "97") (name "Net-(IC10A-D4)") (class "Default")
      (node (ref "IC10") (pin "11") (pinfunction "D4_11") (pintype "input"))
      (node (ref "IC6") (pin "14") (pinfunction "GS_14") (pintype "output"))
      (node (ref "IC8") (pin "12") (pinfunction "I0_12") (pintype "input"))
    )
    (net (code "98") (name "Net-(IC10A-Q1)") (class "Default")
      (node (ref "IC10") (pin "3") (pinfunction "Q1_3") (pintype "tri_state"))
      (node (ref "IC13") (pin "2") (pinfunction "1A_2") (pintype "input"))
    )
    (net (code "99") (name "Net-(IC10A-Q2)") (class "Default")
      (node (ref "IC10") (pin "4") (pinfunction "Q2_4") (pintype "tri_state"))
      (node (ref "IC13") (pin "5") (pinfunction "2A_5") (pintype "input"))
    )
    (net (code "100") (name "Net-(IC10A-Q3)") (class "Default")
      (node (ref "IC10") (pin "5") (pinfunction "Q3_5") (pintype "tri_state"))
      (node (ref "IC13") (pin "11") (pinfunction "3A_11") (pintype "input"))
    )
    (net (code "101") (name "Net-(IC10A-Q4)") (class "Default")
      (node (ref "IC10") (pin "6") (pinfunction "Q4_6") (pintype "tri_state"))
      (node (ref "IC13") (pin "14") (pinfunction "4A_14") (pintype "input"))
    )
    (net (code "102") (name "Net-(IC11A-CLK)") (class "Default")
      (node (ref "IC11") (pin "11") (pinfunction "CLK_11") (pintype "input"))
      (node (ref "IC12") (pin "3") (pinfunction "CLK_3") (pintype "input"))
      (node (ref "IC9") (pin "11") (pinfunction "O_11") (pintype "output"))
    )
    (net (code "103") (name "Net-(IC11A-Q1)") (class "Default")
      (node (ref "IC11") (pin "2") (pinfunction "Q1_2") (pintype "output"))
      (node (ref "IC13") (pin "3") (pinfunction "1B_3") (pintype "input"))
    )
    (net (code "104") (name "Net-(IC11A-Q2)") (class "Default")
      (node (ref "IC11") (pin "5") (pinfunction "Q2_5") (pintype "output"))
      (node (ref "IC13") (pin "6") (pinfunction "2B_6") (pintype "input"))
    )
    (net (code "105") (name "Net-(IC11A-Q3)") (class "Default")
      (node (ref "IC11") (pin "6") (pinfunction "Q3_6") (pintype "output"))
      (node (ref "IC13") (pin "10") (pinfunction "3B_10") (pintype "input"))
    )
    (net (code "106") (name "Net-(IC11A-Q4)") (class "Default")
      (node (ref "IC11") (pin "9") (pinfunction "Q4_9") (pintype "output"))
      (node (ref "IC13") (pin "13") (pinfunction "4B_13") (pintype "input"))
    )
    (net (code "107") (name "Net-(IC11A-Q5)") (class "Default")
      (node (ref "IC11") (pin "12") (pinfunction "Q5_12") (pintype "output"))
      (node (ref "IC14") (pin "3") (pinfunction "1B_3") (pintype "input"))
    )
    (net (code "108") (name "Net-(IC11A-Q6)") (class "Default")
      (node (ref "IC11") (pin "15") (pinfunction "Q6_15") (pintype "output"))
      (node (ref "IC14") (pin "6") (pinfunction "2B_6") (pintype "input"))
    )
    (net (code "109") (name "Net-(IC11A-Q7)") (class "Default")
      (node (ref "IC11") (pin "16") (pinfunction "Q7_16") (pintype "output"))
      (node (ref "IC14") (pin "10") (pinfunction "3B_10") (pintype "input"))
    )
    (net (code "110") (name "Net-(IC11A-Q8)") (class "Default")
      (node (ref "IC11") (pin "19") (pinfunction "Q8_19") (pintype "output"))
      (node (ref "IC14") (pin "13") (pinfunction "4B_13") (pintype "input"))
    )
    (net (code "111") (name "Net-(IC12A-D)") (class "Default")
      (node (ref "IC12") (pin "2") (pinfunction "D_2") (pintype "input"))
      (node (ref "IC8") (pin "11") (pinfunction "O_11") (pintype "output"))
    )
    (net (code "112") (name "Net-(IC12A-Q)") (class "Default")
      (node (ref "IC12") (pin "5") (pinfunction "Q_5") (pintype "output"))
      (node (ref "IC13") (pin "1") (pinfunction "~{A}/B_1") (pintype "input"))
      (node (ref "IC14") (pin "1") (pinfunction "~{A}/B_1") (pintype "input"))
    )
    (net (code "113") (name "Net-(IC15A-LD)") (class "Default")
      (node (ref "IC1") (pin "4") (pinfunction "I0_4") (pintype "input"))
      (node (ref "IC15") (pin "9") (pinfunction "LD_9") (pintype "input"))
      (node (ref "IC16") (pin "9") (pinfunction "LD_9") (pintype "input"))
      (node (ref "IC4") (pin "12") (pinfunction "I0_12") (pintype "input"))
      (node (ref "IC7") (pin "14") (pinfunction "GS_14") (pintype "output"))
      (node (ref "IC8") (pin "13") (pinfunction "I1_13") (pintype "input"))
    )
    (net (code "114") (name "Net-(IC15A-QA)") (class "Default")
      (node (ref "IC15") (pin "14") (pinfunction "QA_14") (pintype "output"))
      (node (ref "IC3") (pin "3") (pinfunction "A_3") (pintype "input"))
    )
    (net (code "115") (name "Net-(IC15A-QB)") (class "Default")
      (node (ref "IC15") (pin "13") (pinfunction "QB_13") (pintype "output"))
      (node (ref "IC3") (pin "4") (pinfunction "B_4") (pintype "input"))
    )
    (net (code "116") (name "Net-(IC15A-QC)") (class "Default")
      (node (ref "IC15") (pin "12") (pinfunction "QC_12") (pintype "output"))
      (node (ref "IC3") (pin "5") (pinfunction "C_5") (pintype "input"))
    )
    (net (code "117") (name "Net-(IC15A-QD)") (class "Default")
      (node (ref "IC15") (pin "11") (pinfunction "QD_11") (pintype "output"))
      (node (ref "IC3") (pin "6") (pinfunction "D_6") (pintype "input"))
    )
    (net (code "118") (name "Net-(IC16A-QA)") (class "Default")
      (node (ref "IC16") (pin "14") (pinfunction "QA_14") (pintype "output"))
      (node (ref "IC2") (pin "3") (pinfunction "A_3") (pintype "input"))
    )
    (net (code "119") (name "Net-(IC16A-QB)") (class "Default")
      (node (ref "IC16") (pin "13") (pinfunction "QB_13") (pintype "output"))
      (node (ref "IC2") (pin "4") (pinfunction "B_4") (pintype "input"))
    )
    (net (code "120") (name "Net-(IC16A-QC)") (class "Default")
      (node (ref "IC16") (pin "12") (pinfunction "QC_12") (pintype "output"))
      (node (ref "IC2") (pin "5") (pinfunction "C_5") (pintype "input"))
    )
    (net (code "121") (name "Net-(IC16A-QD)") (class "Default")
      (node (ref "IC16") (pin "11") (pinfunction "QD_11") (pintype "output"))
      (node (ref "IC2") (pin "6") (pinfunction "D_6") (pintype "input"))
    )
    (net (code "122") (name "Net-(IC17A-O)") (class "Default")
      (node (ref "IC17") (pin "2") (pinfunction "O_2") (pintype "output"))
      (node (ref "IC9") (pin "10") (pinfunction "I1_10") (pintype "input"))
    )
    (net (code "123") (name "OP0") (class "Default")
      (node (ref "IC13") (pin "4") (pinfunction "1Y_4") (pintype "output"))
      (node (ref "JP7") (pin "9") (pinfunction "9_9") (pintype "passive"))
    )
    (net (code "124") (name "OP1") (class "Default")
      (node (ref "IC13") (pin "7") (pinfunction "2Y_7") (pintype "output"))
      (node (ref "JP7") (pin "8") (pinfunction "8_8") (pintype "passive"))
    )
    (net (code "125") (name "OP2") (class "Default")
      (node (ref "IC13") (pin "9") (pinfunction "3Y_9") (pintype "output"))
      (node (ref "JP7") (pin "7") (pinfunction "7_7") (pintype "passive"))
    )
    (net (code "126") (name "OP3") (class "Default")
      (node (ref "IC13") (pin "12") (pinfunction "4Y_12") (pintype "output"))
      (node (ref "JP7") (pin "6") (pinfunction "6_6") (pintype "passive"))
    )
    (net (code "127") (name "OP4") (class "Default")
      (node (ref "IC14") (pin "4") (pinfunction "1Y_4") (pintype "output"))
      (node (ref "JP7") (pin "5") (pinfunction "5_5") (pintype "passive"))
    )
    (net (code "128") (name "OP5") (class "Default")
      (node (ref "IC14") (pin "7") (pinfunction "2Y_7") (pintype "output"))
      (node (ref "JP7") (pin "4") (pinfunction "4_4") (pintype "passive"))
    )
    (net (code "129") (name "OP6") (class "Default")
      (node (ref "IC14") (pin "9") (pinfunction "3Y_9") (pintype "output"))
      (node (ref "JP7") (pin "3") (pinfunction "3_3") (pintype "passive"))
    )
    (net (code "130") (name "OP7") (class "Default")
      (node (ref "IC14") (pin "12") (pinfunction "4Y_12") (pintype "output"))
      (node (ref "JP7") (pin "2") (pinfunction "2_2") (pintype "passive"))
    )
    (net (code "131") (name "OP8") (class "Default")
      (node (ref "IC12") (pin "6") (pinfunction "~{Q}_6") (pintype "output"))
      (node (ref "JP7") (pin "1") (pinfunction "1_1") (pintype "passive"))
    )
    (net (code "132") (name "PROT") (class "Default")
      (node (ref "IC4") (pin "10") (pinfunction "I1_10") (pintype "input"))
      (node (ref "JP10") (pin "21") (pinfunction "21_21") (pintype "passive"))
    )
    (net (code "133") (name "RBUS0") (class "Default")
      (node (ref "JP4") (pin "1") (pinfunction "1_1") (pintype "passive"))
    )
    (net (code "134") (name "RBUS1") (class "Default")
      (node (ref "JP4") (pin "2") (pinfunction "2_2") (pintype "passive"))
    )
    (net (code "135") (name "RBUS2") (class "Default")
      (node (ref "JP4") (pin "3") (pinfunction "3_3") (pintype "passive"))
    )
    (net (code "136") (name "RBUS3") (class "Default")
      (node (ref "JP4") (pin "4") (pinfunction "4_4") (pintype "passive"))
    )
    (net (code "137") (name "RBUS4") (class "Default")
      (node (ref "JP4") (pin "5") (pinfunction "5_5") (pintype "passive"))
    )
    (net (code "138") (name "RBUS5") (class "Default")
      (node (ref "JP4") (pin "6") (pinfunction "6_6") (pintype "passive"))
    )
    (net (code "139") (name "RBUS6") (class "Default")
      (node (ref "JP4") (pin "7") (pinfunction "7_7") (pintype "passive"))
    )
    (net (code "140") (name "RBUS7") (class "Default")
      (node (ref "JP4") (pin "8") (pinfunction "8_8") (pintype "passive"))
    )
    (net (code "141") (name "RBUS8") (class "Default")
      (node (ref "JP4") (pin "9") (pinfunction "9_9") (pintype "passive"))
    )
    (net (code "142") (name "RBUS9") (class "Default")
      (node (ref "JP4") (pin "10") (pinfunction "10_10") (pintype "passive"))
    )
    (net (code "143") (name "RBUS10") (class "Default")
      (node (ref "JP4") (pin "11") (pinfunction "11_11") (pintype "passive"))
    )
    (net (code "144") (name "RBUS11") (class "Default")
      (node (ref "JP4") (pin "12") (pinfunction "12_12") (pintype "passive"))
    )
    (net (code "145") (name "RBUS12") (class "Default")
      (node (ref "JP4") (pin "13") (pinfunction "13_13") (pintype "passive"))
    )
    (net (code "146") (name "RBUS13") (class "Default")
      (node (ref "JP4") (pin "14") (pinfunction "14_14") (pintype "passive"))
    )
    (net (code "147") (name "RBUS14") (class "Default")
      (node (ref "JP4") (pin "15") (pinfunction "15_15") (pintype "passive"))
    )
    (net (code "148") (name "RBUS15") (class "Default")
      (node (ref "JP4") (pin "16") (pinfunction "16_16") (pintype "passive"))
    )
    (net (code "149") (name "RST") (class "Default")
      (node (ref "IC10") (pin "15") (pinfunction "CLR_15") (pintype "input"))
      (node (ref "JP10") (pin "9") (pinfunction "9_9") (pintype "passive"))
    )
    (net (code "150") (name "SP_DIR") (class "Default")
      (node (ref "JP10") (pin "20") (pinfunction "20_20") (pintype "passive"))
    )
    (net (code "151") (name "unconnected-(IC1C-O-Pad8)") (class "Default")
      (node (ref "IC1") (pin "8") (pinfunction "O_8") (pintype "output"))
    )
    (net (code "152") (name "unconnected-(IC1D-O-Pad11)") (class "Default")
      (node (ref "IC1") (pin "11") (pinfunction "O_11") (pintype "output"))
    )
    (net (code "153") (name "unconnected-(IC3A-QB-Pad13)") (class "Default")
      (node (ref "IC3") (pin "13") (pinfunction "QB_13") (pintype "output"))
    )
    (net (code "154") (name "unconnected-(IC3A-QC-Pad12)") (class "Default")
      (node (ref "IC3") (pin "12") (pinfunction "QC_12") (pintype "output"))
    )
    (net (code "155") (name "unconnected-(IC3A-QD-Pad11)") (class "Default")
      (node (ref "IC3") (pin "11") (pinfunction "QD_11") (pintype "output"))
    )
    (net (code "156") (name "unconnected-(IC3A-RCO-Pad15)") (class "Default")
      (node (ref "IC3") (pin "15") (pinfunction "RCO_15") (pintype "output"))
    )
    (net (code "157") (name "unconnected-(IC4A-O-Pad3)") (class "Default")
      (node (ref "IC4") (pin "3") (pinfunction "O_3") (pintype "output"))
    )
    (net (code "158") (name "unconnected-(IC4B-O-Pad6)") (class "Default")
      (node (ref "IC4") (pin "6") (pinfunction "O_6") (pintype "output"))
    )
    (net (code "159") (name "unconnected-(IC6A-EO-Pad15)") (class "Default")
      (node (ref "IC6") (pin "15") (pinfunction "EO_15") (pintype "output"))
    )
    (net (code "160") (name "unconnected-(IC9A-O-Pad3)") (class "Default")
      (node (ref "IC9") (pin "3") (pinfunction "O_3") (pintype "output"))
    )
    (net (code "161") (name "unconnected-(IC12B-Q-Pad9)") (class "Default")
      (node (ref "IC12") (pin "9") (pinfunction "Q_9") (pintype "output"))
    )
    (net (code "162") (name "unconnected-(IC12B-~{Q}-Pad8)") (class "Default")
      (node (ref "IC12") (pin "8") (pinfunction "~{Q}_8") (pintype "output"))
    )
    (net (code "163") (name "unconnected-(IC15A-RCO-Pad15)") (class "Default")
      (node (ref "IC15") (pin "15") (pinfunction "RCO_15") (pintype "output"))
    )
    (net (code "164") (name "unconnected-(IC16A-RCO-Pad15)") (class "Default")
      (node (ref "IC16") (pin "15") (pinfunction "RCO_15") (pintype "output"))
    )
    (net (code "165") (name "unconnected-(IC17B-O-Pad4)") (class "Default")
      (node (ref "IC17") (pin "4") (pinfunction "O_4") (pintype "output"))
    )
    (net (code "166") (name "unconnected-(IC17C-O-Pad6)") (class "Default")
      (node (ref "IC17") (pin "6") (pinfunction "O_6") (pintype "output"))
    )
    (net (code "167") (name "unconnected-(IC17D-O-Pad8)") (class "Default")
      (node (ref "IC17") (pin "8") (pinfunction "O_8") (pintype "output"))
    )
    (net (code "168") (name "unconnected-(IC17E-O-Pad10)") (class "Default")
      (node (ref "IC17") (pin "10") (pinfunction "O_10") (pintype "output"))
    )
    (net (code "169") (name "unconnected-(IC17F-O-Pad12)") (class "Default")
      (node (ref "IC17") (pin "12") (pinfunction "O_12") (pintype "output"))
    )
    (net (code "170") (name "{slash}ALUHI2MEM") (class "Default")
      (node (ref "JP10") (pin "25") (pinfunction "25_25") (pintype "passive"))
    )
    (net (code "171") (name "{slash}ALULO2MEM") (class "Default")
      (node (ref "JP10") (pin "29") (pinfunction "29_29") (pintype "passive"))
    )
    (net (code "172") (name "{slash}BUSIFCEN") (class "Default")
      (node (ref "IC4") (pin "13") (pinfunction "I1_13") (pintype "input"))
      (node (ref "JP10") (pin "5") (pinfunction "5_5") (pintype "passive"))
    )
    (net (code "173") (name "{slash}CNTSP") (class "Default")
      (node (ref "JP10") (pin "3") (pinfunction "3_3") (pintype "passive"))
    )
    (net (code "174") (name "{slash}ENABUS") (class "Default")
      (node (ref "JP10") (pin "22") (pinfunction "22_22") (pintype "passive"))
    )
    (net (code "175") (name "{slash}ENMEM") (class "Default")
      (node (ref "JP10") (pin "16") (pinfunction "16_16") (pintype "passive"))
    )
    (net (code "176") (name "{slash}FI") (class "Default")
      (node (ref "IC9") (pin "4") (pinfunction "I0_4") (pintype "input"))
      (node (ref "JP10") (pin "32") (pinfunction "32_32") (pintype "passive"))
    )
    (net (code "177") (name "{slash}FP") (class "Default")
      (node (ref "JP10") (pin "34") (pinfunction "34_34") (pintype "passive"))
    )
    (net (code "178") (name "{slash}FRET") (class "Default")
      (node (ref "IC17") (pin "1") (pinfunction "I_1") (pintype "input"))
      (node (ref "IC2") (pin "9") (pinfunction "LD_9") (pintype "input"))
      (node (ref "IC3") (pin "9") (pinfunction "LD_9") (pintype "input"))
      (node (ref "JP8") (pin "1") (pinfunction "1_1") (pintype "passive"))
    )
    (net (code "179") (name "{slash}FS") (class "Default")
      (node (ref "IC4") (pin "9") (pinfunction "I0_9") (pintype "input"))
      (node (ref "JP10") (pin "30") (pinfunction "30_30") (pintype "passive"))
    )
    (net (code "180") (name "{slash}INCPC") (class "Default")
      (node (ref "JP10") (pin "1") (pinfunction "1_1") (pintype "passive"))
    )
    (net (code "181") (name "{slash}IO") (class "Default")
      (node (ref "JP10") (pin "35") (pinfunction "35_35") (pintype "passive"))
    )
    (net (code "182") (name "{slash}LATCHFLAGS") (class "Default")
      (node (ref "IC4") (pin "11") (pinfunction "O_11") (pintype "output"))
      (node (ref "JP10") (pin "12") (pinfunction "12_12") (pintype "passive"))
    )
    (net (code "183") (name "{slash}LDMEM") (class "Default")
      (node (ref "JP10") (pin "15") (pinfunction "15_15") (pintype "passive"))
    )
    (net (code "184") (name "{slash}LOAD_IR") (class "Default")
      (node (ref "IC1") (pin "2") (pinfunction "I1_2") (pintype "input"))
      (node (ref "JP10") (pin "26") (pinfunction "26_26") (pintype "passive"))
    )
    (net (code "185") (name "{slash}MEM2ALUHI") (class "Default")
      (node (ref "JP10") (pin "27") (pinfunction "27_27") (pintype "passive"))
    )
    (net (code "186") (name "{slash}MEM2ALULO") (class "Default")
      (node (ref "JP10") (pin "31") (pinfunction "31_31") (pintype "passive"))
    )
    (net (code "187") (name "{slash}MEMOP") (class "Default")
      (node (ref "JP10") (pin "11") (pinfunction "11_11") (pintype "passive"))
    )
    (net (code "188") (name "{slash}NEXTOP") (class "Default")
      (node (ref "IC1") (pin "6") (pinfunction "O_6") (pintype "output"))
      (node (ref "IC10") (pin "10") (pinfunction "G2_10") (pintype "input"))
      (node (ref "IC10") (pin "9") (pinfunction "G1_9") (pintype "input"))
      (node (ref "IC9") (pin "12") (pinfunction "I0_12") (pintype "input"))
      (node (ref "IC9") (pin "9") (pinfunction "I0_9") (pintype "input"))
    )
    (net (code "189") (name "{slash}NP_FAULT") (class "Default")
      (node (ref "IC7") (pin "3") (pinfunction "6_3") (pintype "input"))
      (node (ref "JP10") (pin "36") (pinfunction "36_36") (pintype "passive"))
    )
    (net (code "190") (name "{slash}RST") (class "Default")
      (node (ref "IC1") (pin "1") (pinfunction "I0_1") (pintype "input"))
      (node (ref "IC11") (pin "1") (pinfunction "CLR_1") (pintype "input"))
      (node (ref "IC12") (pin "4") (pinfunction "PRE_4") (pintype "input"))
      (node (ref "JP10") (pin "7") (pinfunction "7_7") (pintype "passive"))
    )
    (net (code "191") (name "{slash}WR_FAULT") (class "Default")
      (node (ref "IC7") (pin "2") (pinfunction "5_2") (pintype "input"))
      (node (ref "JP10") (pin "33") (pinfunction "33_33") (pintype "passive"))
    )
  )
)
